# lora.net
KiCad netlist of a schematic drawn in Altium Designer
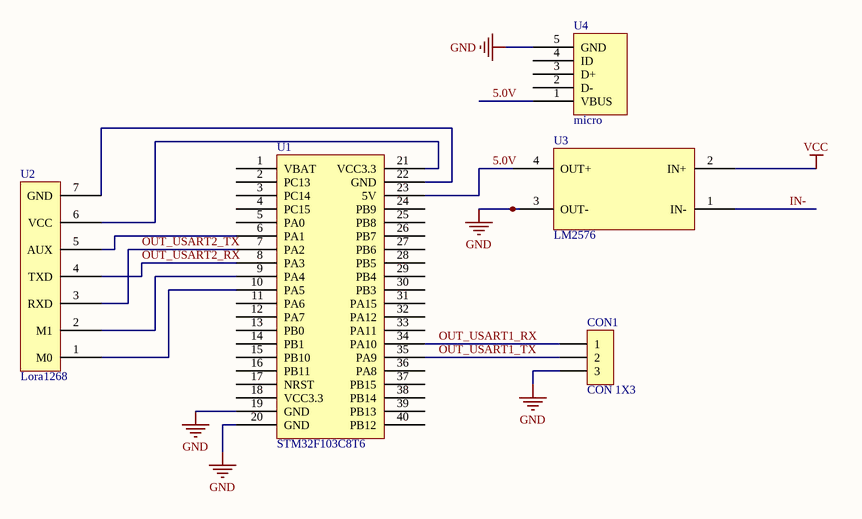
[diagram p0: lora.SchDoc]

(export (version "E")
  (design (tool "Eeschema 10.0.6"))
  (components
    (comp (ref "CON1")
      (value "CON 1X3")
      (footprint "CON 1X3")
      (description "单排排针")
      (libsource (lib "常用接插件") (part "CON 1X3"))
    )
    (comp (ref "U1")
      (value "STM32F103C8T6")
      (footprint "STM32C8T6")
      (libsource (lib "模块封装库") (part "STM32C8T6"))
    )
    (comp (ref "U2") (value "Lora1268") (footprint "Lora模块") (libsource (lib "lora") (part "Lora1268")))
    (comp (ref "U3") (value "LM2576") (footprint "LM2576") (libsource (lib "模块封装库") (part "LM2576")))
    (comp (ref "U4") (value "micro") (footprint "micro") (libsource (lib "lora") (part "micro")))
  )
  (nets
    (net (code "1") (name "/5.0V") (class "Default")
      (node (ref "U1") (pin "23") (pinfunction "5V_23") (pintype "passive"))
      (node (ref "U3") (pin "4") (pinfunction "OUT+_4") (pintype "passive"))
      (node (ref "U4") (pin "1") (pinfunction "VBUS_1") (pintype "passive"))
    )
    (net (code "2") (name "/IN-") (class "Default")
      (node (ref "U3") (pin "1") (pinfunction "IN-_1") (pintype "passive"))
    )
    (net (code "3") (name "/OUT_USART1_RX") (class "Default")
      (node (ref "CON1") (pin "1") (pinfunction "1_1") (pintype "passive"))
      (node (ref "U1") (pin "34") (pinfunction "PA10_34") (pintype "passive"))
    )
    (net (code "4") (name "/OUT_USART1_TX") (class "Default")
      (node (ref "CON1") (pin "2") (pinfunction "2_2") (pintype "passive"))
      (node (ref "U1") (pin "35") (pinfunction "PA9_35") (pintype "passive"))
    )
    (net (code "5") (name "/OUT_USART2_RX") (class "Default")
      (node (ref "U1") (pin "8") (pinfunction "PA3_8") (pintype "passive"))
      (node (ref "U2") (pin "4") (pinfunction "TXD_4") (pintype "passive"))
    )
    (net (code "6") (name "/OUT_USART2_TX") (class "Default")
      (node (ref "U1") (pin "7") (pinfunction "PA2_7") (pintype "passive"))
      (node (ref "U2") (pin "3") (pinfunction "RXD_3") (pintype "passive"))
    )
    (net (code "7") (name "GND") (class "Default")
      (node (ref "CON1") (pin "3") (pinfunction "3_3") (pintype "passive"))
      (node (ref "U1") (pin "19") (pinfunction "GND_19") (pintype "passive"))
      (node (ref "U1") (pin "20") (pinfunction "GND_20") (pintype "passive"))
      (node (ref "U3") (pin "3") (pinfunction "OUT-_3") (pintype "passive"))
      (node (ref "U4") (pin "5") (pinfunction "GND_5") (pintype "passive"))
    )
    (net (code "8") (name "Net-(U1-PA1)") (class "Default")
      (node (ref "U1") (pin "6") (pinfunction "PA1_6") (pintype "passive"))
      (node (ref "U2") (pin "5") (pinfunction "AUX_5") (pintype "passive"))
    )
    (net (code "9") (name "Net-(U1-PA4)") (class "Default")
      (node (ref "U1") (pin "9") (pinfunction "PA4_9") (pintype "passive"))
      (node (ref "U2") (pin "2") (pinfunction "M1_2") (pintype "passive"))
    )
    (net (code "10") (name "Net-(U1-PA5)") (class "Default")
      (node (ref "U1") (pin "10") (pinfunction "PA5_10") (pintype "passive"))
      (node (ref "U2") (pin "1") (pinfunction "M0_1") (pintype "passive"))
    )
    (net (code "11") (name "Net-(U2-GND)") (class "Default")
      (node (ref "U1") (pin "22") (pinfunction "GND_22") (pintype "passive"))
      (node (ref "U2") (pin "7") (pinfunction "GND_7") (pintype "passive"))
    )
    (net (code "12") (name "Net-(U2-VCC)") (class "Default")
      (node (ref "U1") (pin "21") (pinfunction "VCC3.3_21") (pintype "passive"))
      (node (ref "U2") (pin "6") (pinfunction "VCC_6") (pintype "passive"))
    )
    (net (code "13") (name "VCC") (class "Default")
      (node (ref "U3") (pin "2") (pinfunction "IN+_2") (pintype "passive"))
    )
    (net (code "14") (name "unconnected-(U1-NRST-Pad17)") (class "Default")
      (node (ref "U1") (pin "17") (pinfunction "NRST_17") (pintype "passive"))
    )
    (net (code "15") (name "unconnected-(U1-PA0-Pad5)") (class "Default")
      (node (ref "U1") (pin "5") (pinfunction "PA0_5") (pintype "passive"))
    )
    (net (code "16") (name "unconnected-(U1-PA6-Pad11)") (class "Default")
      (node (ref "U1") (pin "11") (pinfunction "PA6_11") (pintype "passive"))
    )
    (net (code "17") (name "unconnected-(U1-PA7-Pad12)") (class "Default")
      (node (ref "U1") (pin "12") (pinfunction "PA7_12") (pintype "passive"))
    )
    (net (code "18") (name "unconnected-(U1-PA8-Pad36)") (class "Default")
      (node (ref "U1") (pin "36") (pinfunction "PA8_36") (pintype "passive"))
    )
    (net (code "19") (name "unconnected-(U1-PA11-Pad33)") (class "Default")
      (node (ref "U1") (pin "33") (pinfunction "PA11_33") (pintype "passive"))
    )
    (net (code "20") (name "unconnected-(U1-PA12-Pad32)") (class "Default")
      (node (ref "U1") (pin "32") (pinfunction "PA12_32") (pintype "passive"))
    )
    (net (code "21") (name "unconnected-(U1-PA15-Pad31)") (class "Default")
      (node (ref "U1") (pin "31") (pinfunction "PA15_31") (pintype "passive"))
    )
    (net (code "22") (name "unconnected-(U1-PB0-Pad13)") (class "Default")
      (node (ref "U1") (pin "13") (pinfunction "PB0_13") (pintype "passive"))
    )
    (net (code "23") (name "unconnected-(U1-PB1-Pad14)") (class "Default")
      (node (ref "U1") (pin "14") (pinfunction "PB1_14") (pintype "passive"))
    )
    (net (code "24") (name "unconnected-(U1-PB3-Pad30)") (class "Default")
      (node (ref "U1") (pin "30") (pinfunction "PB3_30") (pintype "passive"))
    )
    (net (code "25") (name "unconnected-(U1-PB4-Pad29)") (class "Default")
      (node (ref "U1") (pin "29") (pinfunction "PB4_29") (pintype "passive"))
    )
    (net (code "26") (name "unconnected-(U1-PB5-Pad28)") (class "Default")
      (node (ref "U1") (pin "28") (pinfunction "PB5_28") (pintype "passive"))
    )
    (net (code "27") (name "unconnected-(U1-PB6-Pad27)") (class "Default")
      (node (ref "U1") (pin "27") (pinfunction "PB6_27") (pintype "passive"))
    )
    (net (code "28") (name "unconnected-(U1-PB7-Pad26)") (class "Default")
      (node (ref "U1") (pin "26") (pinfunction "PB7_26") (pintype "passive"))
    )
    (net (code "29") (name "unconnected-(U1-PB8-Pad25)") (class "Default")
      (node (ref "U1") (pin "25") (pinfunction "PB8_25") (pintype "passive"))
    )
    (net (code "30") (name "unconnected-(U1-PB9-Pad24)") (class "Default")
      (node (ref "U1") (pin "24") (pinfunction "PB9_24") (pintype "passive"))
    )
    (net (code "31") (name "unconnected-(U1-PB10-Pad15)") (class "Default")
      (node (ref "U1") (pin "15") (pinfunction "PB10_15") (pintype "passive"))
    )
    (net (code "32") (name "unconnected-(U1-PB11-Pad16)") (class "Default")
      (node (ref "U1") (pin "16") (pinfunction "PB11_16") (pintype "passive"))
    )
    (net (code "33") (name "unconnected-(U1-PB12-Pad40)") (class "Default")
      (node (ref "U1") (pin "40") (pinfunction "PB12_40") (pintype "passive"))
    )
    (net (code "34") (name "unconnected-(U1-PB13-Pad39)") (class "Default")
      (node (ref "U1") (pin "39") (pinfunction "PB13_39") (pintype "passive"))
    )
    (net (code "35") (name "unconnected-(U1-PB14-Pad38)") (class "Default")
      (node (ref "U1") (pin "38") (pinfunction "PB14_38") (pintype "passive"))
    )
    (net (code "36") (name "unconnected-(U1-PB15-Pad37)") (class "Default")
      (node (ref "U1") (pin "37") (pinfunction "PB15_37") (pintype "passive"))
    )
    (net (code "37") (name "unconnected-(U1-PC13-Pad2)") (class "Default")
      (node (ref "U1") (pin "2") (pinfunction "PC13_2") (pintype "passive"))
    )
    (net (code "38") (name "unconnected-(U1-PC14-Pad3)") (class "Default")
      (node (ref "U1") (pin "3") (pinfunction "PC14_3") (pintype "passive"))
    )
    (net (code "39") (name "unconnected-(U1-PC15-Pad4)") (class "Default")
      (node (ref "U1") (pin "4") (pinfunction "PC15_4") (pintype "passive"))
    )
    (net (code "40") (name "unconnected-(U1-VBAT-Pad1)") (class "Default")
      (node (ref "U1") (pin "1") (pinfunction "VBAT_1") (pintype "passive"))
    )
    (net (code "41") (name "unconnected-(U1-VCC3.3-Pad18)") (class "Default")
      (node (ref "U1") (pin "18") (pinfunction "VCC3.3_18") (pintype "passive"))
    )
    (net (code "42") (name "unconnected-(U4-D+-Pad3)") (class "Default")
      (node (ref "U4") (pin "3") (pinfunction "D+_3") (pintype "passive"))
    )
    (net (code "43") (name "unconnected-(U4-D--Pad2)") (class "Default")
      (node (ref "U4") (pin "2") (pinfunction "D-_2") (pintype "passive"))
    )
    (net (code "44") (name "unconnected-(U4-ID-Pad4)") (class "Default")
      (node (ref "U4") (pin "4") (pinfunction "ID_4") (pintype "passive"))
    )
  )
)
